# Power.net
KiCad netlist of a schematic drawn in Altium Designer
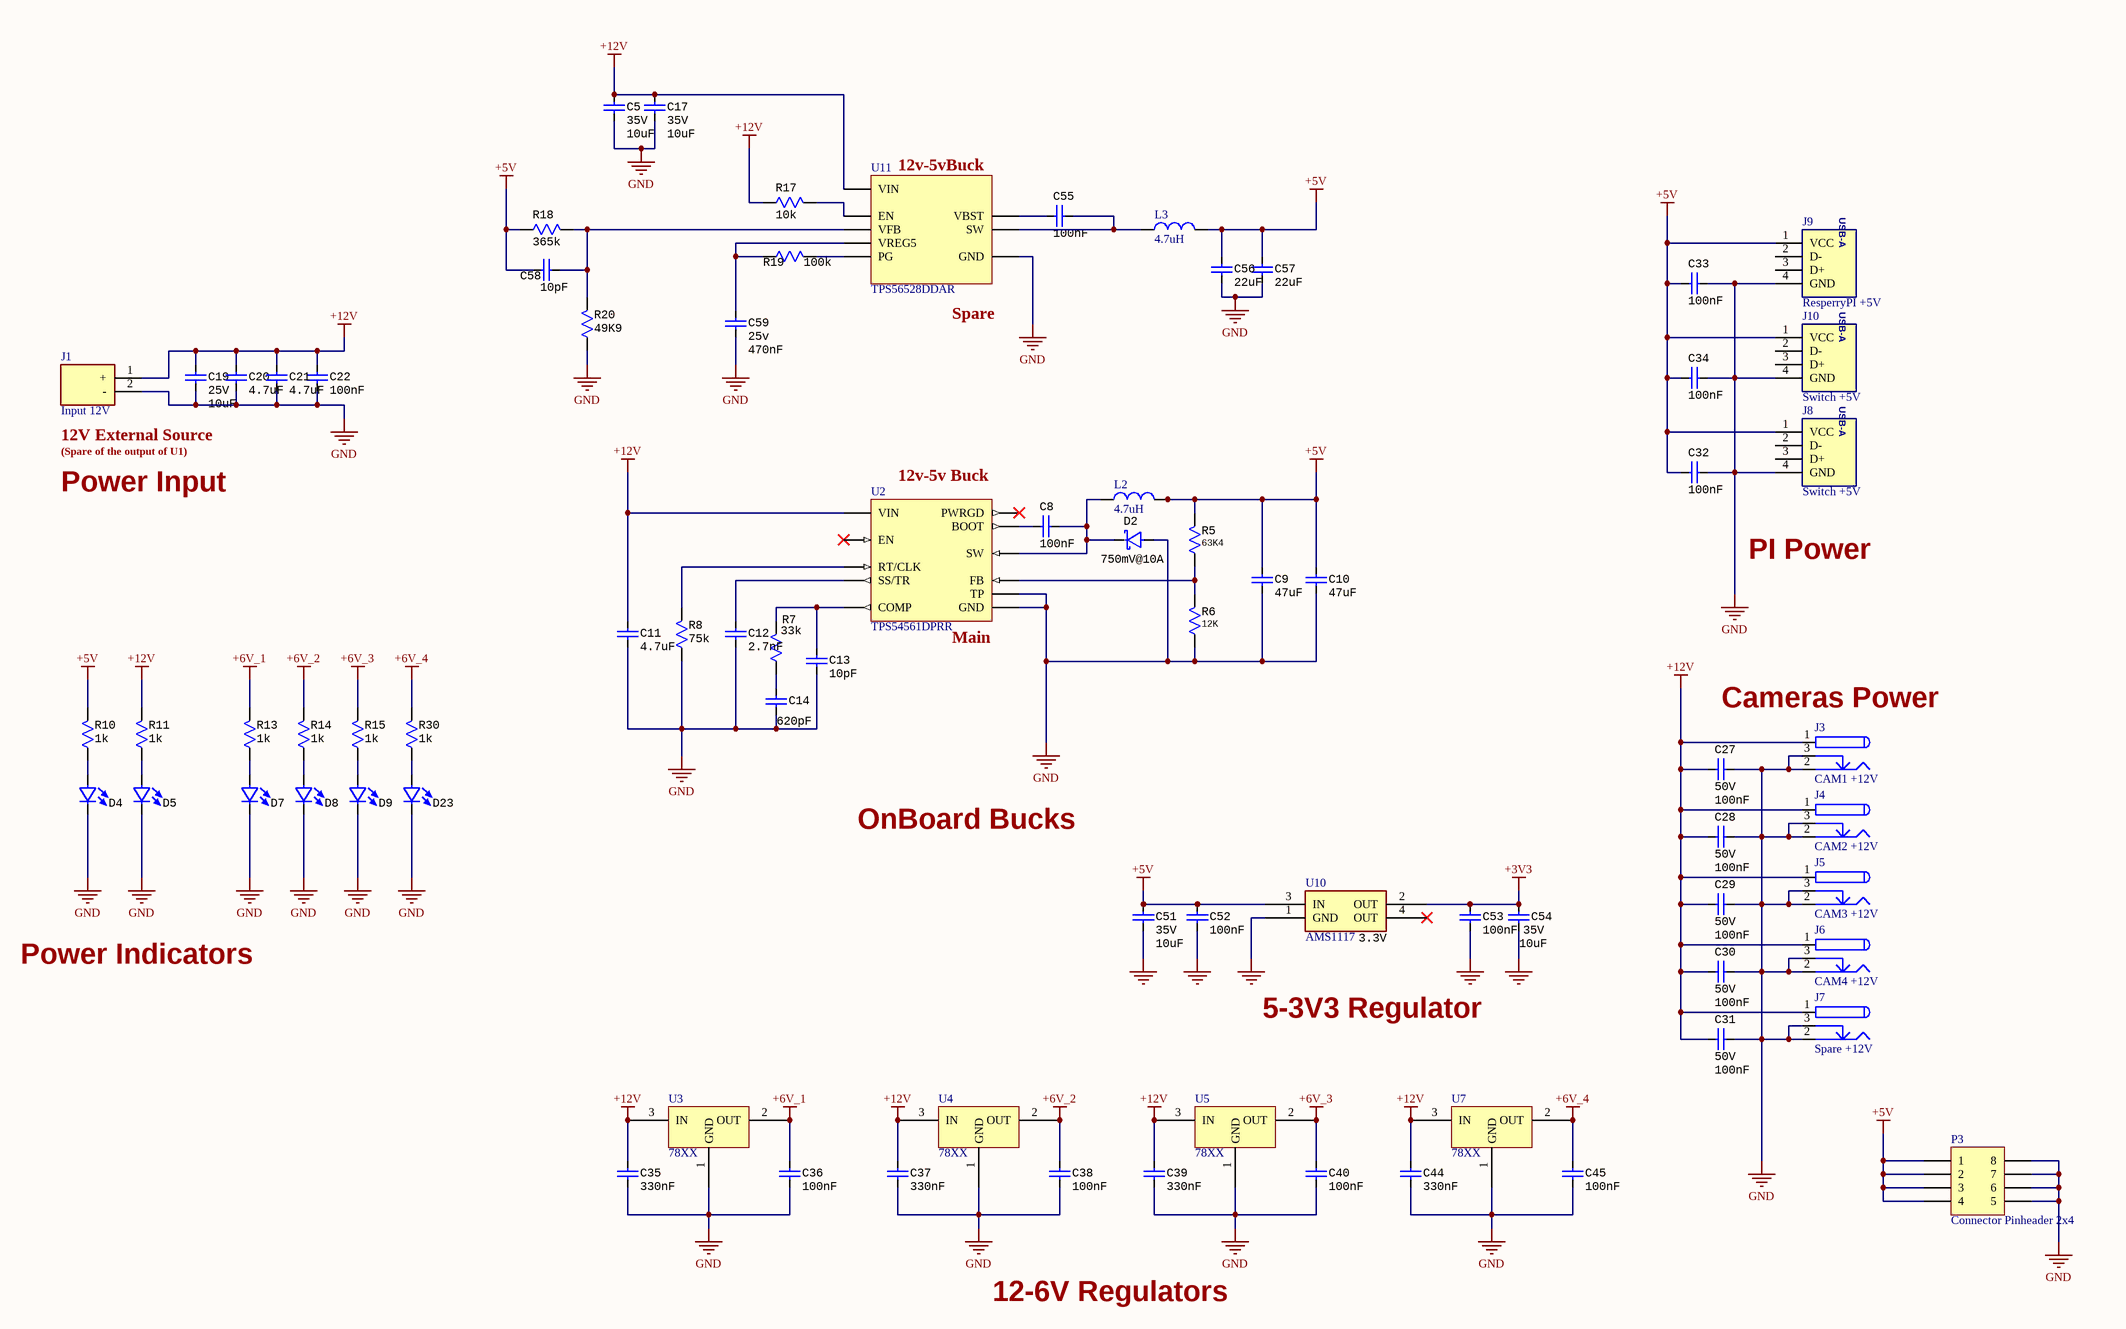
[diagram p0: Power.SchDoc]

(export (version "E")
  (design (tool "Eeschema 10.0.6"))
  (components
    (comp (ref "C5")
      (value "10uF")
      (footprint "CAP Ceramic SMD 0603")
      (description "Cap Ceramic 10uF 35V X5R 20% Pad SMD 0603 85C T/R")
      (fields
        (field (name "MANUFACTURER") "Murata")
        (field (name "MANUFACTURER PART NUMBER") "GRM188R6YA106MA73D")
        (field (name "VOLTAGE") "35V")
      )
      (libsource (lib "Passive") (part "CAP 0603 10uF 35V"))
    )
    (comp (ref "C8")
      (value "100nF")
      (footprint "CAP Ceramic SMD 0603")
      (description "0603 0.1 uF 100 V ±10% Tolerance X7R Multilayer Ceramic Capacitor")
      (fields
        (field (name "MANUFACTURER") "Yageo")
        (field (name "MANUFACTURER PART NUMBER") "CC0603KRX7R0BB104")
      )
      (libsource (lib "capacitor") (part "CAP 0603 100nF 100V"))
    )
    (comp (ref "C9")
      (value "47uF")
      (footprint "CAP Ceramic SMD 1206")
      (description "CAP CER 47UF 10V X5R 1206")
      (fields
        (field (name "MANUFACTURER") "Murata")
        (field (name "MANUFACTURER PART NUMBER") "GRM31CR61A476ME15L")
      )
      (libsource (lib "Passive") (part "CAP 1206 47uF 10V"))
    )
    (comp (ref "C10")
      (value "47uF")
      (footprint "CAP Ceramic SMD 1206")
      (description "CAP CER 47UF 10V X5R 1206")
      (fields
        (field (name "MANUFACTURER") "Murata")
        (field (name "MANUFACTURER PART NUMBER") "GRM31CR61A476ME15L")
      )
      (libsource (lib "Passive") (part "CAP 1206 47uF 10V"))
    )
    (comp (ref "C11")
      (value "4.7uF")
      (footprint "CAP Ceramic SMD 1206")
      (description "Cap Ceramic 4.7uF 100V X7S 10% SMD 1206 125°C Emboss T/R")
      (fields
        (field (name "MANUFACTURER PART NUMBER") "GRM31CC72A475KE11L")
        (field (name "MANUFACTURER") "Murata")
      )
      (libsource (lib "Passive") (part "CAP 1206 4.7uF 100V"))
    )
    (comp (ref "C12")
      (value "2.7nF")
      (footprint "CAP Ceramic SMD 0603")
      (description "0603 2.7 nF 50 V ±10 % Tolerance X7R SMT Multilayer Ceramic Capacitor")
      (fields
        (field (name "MANUFACTURER") "Yageo")
        (field (name "MANUFACTURER PART NUMBER") "CC0603KRX7R9BB272")
      )
      (libsource (lib "Passive") (part "CAP 0603 2.7nF 50V"))
    )
    (comp (ref "C13")
      (value "10pF")
      (footprint "CAP Ceramic SMD 0603")
      (description "Surface Mount Ceramic Multilayer Capacitor 10pF 5% C0G 50V 0603 Paper T/R")
      (fields
        (field (name "MANUFACTURER") "Yageo")
        (field (name "MANUFACTURER PART NUMBER") "CC0603JRNPO9BN100")
      )
      (libsource (lib "Passive") (part "CAP 0603 10pF 50V"))
    )
    (comp (ref "C14")
      (value "620pF")
      (footprint "CAP Ceramic SMD 0603")
      (description "Surface Mount Ceramic Multilayer Capacitor 620pF 5% C0G 50V 0603 Paper T/R")
      (fields
        (field (name "MANUFACTURER") "Yageo")
        (field (name "MANUFACTURER PART NUMBER") "CC0603JRNPO9BN621")
      )
      (libsource (lib "Passive") (part "CAP 0603 620pF 50V"))
    )
    (comp (ref "C17")
      (value "10uF")
      (footprint "CAP Ceramic SMD 0603")
      (description "Cap Ceramic 10uF 35V X5R 20% Pad SMD 0603 85C T/R")
      (fields
        (field (name "MANUFACTURER") "Murata")
        (field (name "MANUFACTURER PART NUMBER") "GRM188R6YA106MA73D")
        (field (name "VOLTAGE") "35V")
      )
      (libsource (lib "Passive") (part "CAP 0603 10uF 35V"))
    )
    (comp (ref "C19")
      (value "10uF")
      (footprint "CAP Ceramic SMD 1206")
      (description "Ceramic capacitor SMD-1206 10000nF (10uF) /25V X7R# K 10%, Samsung, RoHS/4k/")
      (fields
        (field (name "MANUFACTURER") "Samsung")
        (field (name "MANUFACTURER PART NUMBER") "CL31B106KAHNNNE")
        (field (name "VOLTAGE") "25V")
      )
      (libsource (lib "Passive") (part "CAP 1206 10uF 25V"))
    )
    (comp (ref "C20")
      (value "4.7uF")
      (footprint "CAP Ceramic SMD 1206")
      (description "Cap Ceramic 4.7uF 100V X7S 10% SMD 1206 125°C Emboss T/R")
      (fields
        (field (name "MANUFACTURER PART NUMBER") "GRM31CC72A475KE11L")
        (field (name "MANUFACTURER") "Murata")
      )
      (libsource (lib "Passive") (part "CAP 1206 4.7uF 100V"))
    )
    (comp (ref "C21")
      (value "4.7uF")
      (footprint "CAP Ceramic SMD 1206")
      (description "Cap Ceramic 4.7uF 100V X7S 10% SMD 1206 125°C Emboss T/R")
      (fields
        (field (name "MANUFACTURER PART NUMBER") "GRM31CC72A475KE11L")
        (field (name "MANUFACTURER") "Murata")
      )
      (libsource (lib "Passive") (part "CAP 1206 4.7uF 100V"))
    )
    (comp (ref "C22")
      (value "100nF")
      (footprint "CAP Ceramic SMD 0603")
      (description "0603 0.1 uF 100 V ±10% Tolerance X7R Multilayer Ceramic Capacitor")
      (fields
        (field (name "MANUFACTURER") "Yageo")
        (field (name "MANUFACTURER PART NUMBER") "CC0603KRX7R0BB104")
      )
      (libsource (lib "capacitor") (part "CAP 0603 100nF 100V"))
    )
    (comp (ref "C27")
      (value "100nF")
      (footprint "CAP Ceramic SMD 0603")
      (description "Multilayer Ceramic Capacitors MLCC Surface Mount 0603 0.1uF 50 Volts X7R 10%")
      (fields
        (field (name "MANUFACTURER") "Murata")
        (field (name "MANUFACTURER PART NUMBER") "GRM188R71H104KA93D")
        (field (name "VOLTAGE") "50V")
      )
      (libsource (lib "Passive") (part "CAP 0603 100nF 50V"))
    )
    (comp (ref "C28")
      (value "100nF")
      (footprint "CAP Ceramic SMD 0603")
      (description "Multilayer Ceramic Capacitors MLCC Surface Mount 0603 0.1uF 50 Volts X7R 10%")
      (fields
        (field (name "MANUFACTURER") "Murata")
        (field (name "MANUFACTURER PART NUMBER") "GRM188R71H104KA93D")
        (field (name "VOLTAGE") "50V")
      )
      (libsource (lib "Passive") (part "CAP 0603 100nF 50V"))
    )
    (comp (ref "C29")
      (value "100nF")
      (footprint "CAP Ceramic SMD 0603")
      (description "Multilayer Ceramic Capacitors MLCC Surface Mount 0603 0.1uF 50 Volts X7R 10%")
      (fields
        (field (name "MANUFACTURER") "Murata")
        (field (name "MANUFACTURER PART NUMBER") "GRM188R71H104KA93D")
        (field (name "VOLTAGE") "50V")
      )
      (libsource (lib "Passive") (part "CAP 0603 100nF 50V"))
    )
    (comp (ref "C30")
      (value "100nF")
      (footprint "CAP Ceramic SMD 0603")
      (description "Multilayer Ceramic Capacitors MLCC Surface Mount 0603 0.1uF 50 Volts X7R 10%")
      (fields
        (field (name "MANUFACTURER") "Murata")
        (field (name "MANUFACTURER PART NUMBER") "GRM188R71H104KA93D")
        (field (name "VOLTAGE") "50V")
      )
      (libsource (lib "Passive") (part "CAP 0603 100nF 50V"))
    )
    (comp (ref "C31")
      (value "100nF")
      (footprint "CAP Ceramic SMD 0603")
      (description "Multilayer Ceramic Capacitors MLCC Surface Mount 0603 0.1uF 50 Volts X7R 10%")
      (fields
        (field (name "MANUFACTURER") "Murata")
        (field (name "MANUFACTURER PART NUMBER") "GRM188R71H104KA93D")
        (field (name "VOLTAGE") "50V")
      )
      (libsource (lib "Passive") (part "CAP 0603 100nF 50V"))
    )
    (comp (ref "C32")
      (value "100nF")
      (footprint "CAP Ceramic SMD 0603")
      (description "0603 0.1 uF 100 V ±10% Tolerance X7R Multilayer Ceramic Capacitor")
      (fields
        (field (name "MANUFACTURER") "Yageo")
        (field (name "MANUFACTURER PART NUMBER") "CC0603KRX7R0BB104")
      )
      (libsource (lib "capacitor") (part "CAP 0603 100nF 100V"))
    )
    (comp (ref "C33")
      (value "100nF")
      (footprint "CAP Ceramic SMD 0603")
      (description "0603 0.1 uF 100 V ±10% Tolerance X7R Multilayer Ceramic Capacitor")
      (fields
        (field (name "MANUFACTURER") "Yageo")
        (field (name "MANUFACTURER PART NUMBER") "CC0603KRX7R0BB104")
      )
      (libsource (lib "capacitor") (part "CAP 0603 100nF 100V"))
    )
    (comp (ref "C34")
      (value "100nF")
      (footprint "CAP Ceramic SMD 0603")
      (description "0603 0.1 uF 100 V ±10% Tolerance X7R Multilayer Ceramic Capacitor")
      (fields
        (field (name "MANUFACTURER") "Yageo")
        (field (name "MANUFACTURER PART NUMBER") "CC0603KRX7R0BB104")
      )
      (libsource (lib "capacitor") (part "CAP 0603 100nF 100V"))
    )
    (comp (ref "C35")
      (value "330nF")
      (footprint "CAP Ceramic SMD 0603")
      (description "Multilayer Ceramic Capacitor, 0.33 uF, 50 V, ± 10%, X7R, 0603 [1608 Metric]")
      (fields
        (field (name "MANUFACTURER") "TDK")
        (field (name "MANUFACTURER PART NUMBER") "C1608X7R1H334K080AC")
      )
      (libsource (lib "Passive") (part "CAP 0603 330nF 50V"))
    )
    (comp (ref "C36")
      (value "100nF")
      (footprint "CAP Ceramic SMD 0603")
      (description "0603 0.1 uF 100 V ±10% Tolerance X7R Multilayer Ceramic Capacitor")
      (fields
        (field (name "MANUFACTURER") "Yageo")
        (field (name "MANUFACTURER PART NUMBER") "CC0603KRX7R0BB104")
      )
      (libsource (lib "Passive") (part "CAP 0603 100nF 100V"))
    )
    (comp (ref "C37")
      (value "330nF")
      (footprint "CAP Ceramic SMD 0603")
      (description "Multilayer Ceramic Capacitor, 0.33 uF, 50 V, ± 10%, X7R, 0603 [1608 Metric]")
      (fields
        (field (name "MANUFACTURER") "TDK")
        (field (name "MANUFACTURER PART NUMBER") "C1608X7R1H334K080AC")
      )
      (libsource (lib "Passive") (part "CAP 0603 330nF 50V"))
    )
    (comp (ref "C38")
      (value "100nF")
      (footprint "CAP Ceramic SMD 0603")
      (description "0603 0.1 uF 100 V ±10% Tolerance X7R Multilayer Ceramic Capacitor")
      (fields
        (field (name "MANUFACTURER") "Yageo")
        (field (name "MANUFACTURER PART NUMBER") "CC0603KRX7R0BB104")
      )
      (libsource (lib "Passive") (part "CAP 0603 100nF 100V"))
    )
    (comp (ref "C39")
      (value "330nF")
      (footprint "CAP Ceramic SMD 0603")
      (description "Multilayer Ceramic Capacitor, 0.33 uF, 50 V, ± 10%, X7R, 0603 [1608 Metric]")
      (fields
        (field (name "MANUFACTURER") "TDK")
        (field (name "MANUFACTURER PART NUMBER") "C1608X7R1H334K080AC")
      )
      (libsource (lib "Passive") (part "CAP 0603 330nF 50V"))
    )
    (comp (ref "C40")
      (value "100nF")
      (footprint "CAP Ceramic SMD 0603")
      (description "0603 0.1 uF 100 V ±10% Tolerance X7R Multilayer Ceramic Capacitor")
      (fields
        (field (name "MANUFACTURER") "Yageo")
        (field (name "MANUFACTURER PART NUMBER") "CC0603KRX7R0BB104")
      )
      (libsource (lib "Passive") (part "CAP 0603 100nF 100V"))
    )
    (comp (ref "C44")
      (value "330nF")
      (footprint "CAP Ceramic SMD 0603")
      (description "Multilayer Ceramic Capacitor, 0.33 uF, 50 V, ± 10%, X7R, 0603 [1608 Metric]")
      (fields
        (field (name "MANUFACTURER") "TDK")
        (field (name "MANUFACTURER PART NUMBER") "C1608X7R1H334K080AC")
      )
      (libsource (lib "Passive") (part "CAP 0603 330nF 50V"))
    )
    (comp (ref "C45")
      (value "100nF")
      (footprint "CAP Ceramic SMD 0603")
      (description "0603 0.1 uF 100 V ±10% Tolerance X7R Multilayer Ceramic Capacitor")
      (fields
        (field (name "MANUFACTURER") "Yageo")
        (field (name "MANUFACTURER PART NUMBER") "CC0603KRX7R0BB104")
      )
      (libsource (lib "Passive") (part "CAP 0603 100nF 100V"))
    )
    (comp (ref "C51")
      (value "10uF")
      (footprint "CAP Ceramic SMD 0603")
      (description "Cap Ceramic 10uF 35V X5R 20% Pad SMD 0603 85C T/R")
      (fields
        (field (name "MANUFACTURER") "Murata")
        (field (name "MANUFACTURER PART NUMBER") "GRM188R6YA106MA73D")
        (field (name "VOLTAGE") "35V")
      )
      (libsource (lib "Passive") (part "CAP 0603 10uF 35V"))
    )
    (comp (ref "C52")
      (value "100nF")
      (footprint "CAP Ceramic SMD 0603")
      (description "0603 0.1 uF 100 V ±10% Tolerance X7R Multilayer Ceramic Capacitor")
      (fields
        (field (name "MANUFACTURER") "Yageo")
        (field (name "MANUFACTURER PART NUMBER") "AC0603KRX7R0BB104")
      )
      (libsource (lib "capacitor") (part "CAP 0603 100nF 100V"))
    )
    (comp (ref "C53")
      (value "100nF")
      (footprint "CAP Ceramic SMD 0603")
      (description "0603 0.1 uF 100 V ±10% Tolerance X7R Multilayer Ceramic Capacitor")
      (fields
        (field (name "MANUFACTURER") "Yageo")
        (field (name "MANUFACTURER PART NUMBER") "AC0603KRX7R0BB104")
      )
      (libsource (lib "capacitor") (part "CAP 0603 100nF 100V"))
    )
    (comp (ref "C54")
      (value "10uF")
      (footprint "CAP Ceramic SMD 0603")
      (description "Cap Ceramic 10uF 35V X5R 20% Pad SMD 0603 85C T/R")
      (fields
        (field (name "MANUFACTURER") "Murata")
        (field (name "MANUFACTURER PART NUMBER") "GRM188R6YA106MA73D")
        (field (name "VOLTAGE") "35V")
      )
      (libsource (lib "Passive") (part "CAP 0603 10uF 35V"))
    )
    (comp (ref "C55")
      (value "100nF")
      (footprint "CAP Ceramic SMD 0603")
      (description "0603 0.1 uF 100 V ±10% Tolerance X7R Multilayer Ceramic Capacitor")
      (fields
        (field (name "MANUFACTURER") "Yageo")
        (field (name "MANUFACTURER PART NUMBER") "CC0603KRX7R0BB104")
      )
      (libsource (lib "Passive") (part "CAP 0603 100nF 100V"))
    )
    (comp (ref "C56")
      (value "22uF")
      (footprint "CAP Ceramic SMD 0603")
      (description "6.3V 22uF X5R ±20% 0603 Multilayer Ceramic Capacitors MLCC - SMD/SMT ROHS")
      (fields
        (field (name "MANUFACTURER") "YAGEO")
        (field (name "VOLTAGE") "6.3V")
        (field (name "CAPACITANCE") "22uF")
      )
      (libsource (lib "Passive") (part "CAP 0603 22uF 16V"))
    )
    (comp (ref "C57")
      (value "22uF")
      (footprint "CAP Ceramic SMD 0603")
      (description "6.3V 22uF X5R ±20% 0603 Multilayer Ceramic Capacitors MLCC - SMD/SMT ROHS")
      (fields
        (field (name "MANUFACTURER") "YAGEO")
        (field (name "VOLTAGE") "6.3V")
        (field (name "CAPACITANCE") "22uF")
      )
      (libsource (lib "Passive") (part "CAP 0603 22uF 16V"))
    )
    (comp (ref "C58")
      (value "10pF")
      (footprint "CAP Ceramic SMD 0603")
      (description "Surface Mount Ceramic Multilayer Capacitor 10pF 5% C0G 50V 0603 Paper T/R")
      (fields
        (field (name "MANUFACTURER") "Yageo")
        (field (name "MANUFACTURER PART NUMBER") "CC0603JRNPO9BN100")
      )
      (libsource (lib "Passive") (part "CAP 0603 10pF 50V"))
    )
    (comp (ref "C59")
      (value "470nF")
      (footprint "CAP Ceramic SMD 0603")
      (description "25V 470nF X7R 0603 Multilayer Ceramic Capacitors MLCC - SMD/SMT ROHS")
      (fields
        (field (name "MANUFACTURER") "Samwha Capacitor")
        (field (name "MANUFACTURER PART NUMBER") "CS1608X7R474K250NRB")
        (field (name "VOLTAGE") "25v")
      )
      (libsource (lib "capacitor") (part "CAP 0603 470F 25V"))
    )
    (comp (ref "D2")
      (value "750mV@10A")
      (footprint "TO-277")
      (description "100V 750mV@10A 10A TO-277 Schottky Barrier Diodes (SBD) ROHS")
      (fields (field (name "MANUFACTURER") "MDD") (field (name "MANUFACTURER PART NUMBER") "SB10100L"))
      (libsource (lib "diode") (part "Schottky 100V 750mV@10A"))
    )
    (comp (ref "D4")
      (value "~")
      (footprint "LED SMD 0805G")
      (description "emerald 0805 Light Emitting Diodes (LED) ROHS")
      (fields
        (field (name "MANUFACTURER") "FOSHAN Nationstar Optoelectronics")
        (field (name "MANUFACTURER PART NUMBER") "NCD0805G1")
      )
      (libsource (lib "diode") (part "LED 0805 Emerald"))
    )
    (comp (ref "D5")
      (value "~")
      (footprint "LED SMD 0805G")
      (description "emerald 0805 Light Emitting Diodes (LED) ROHS")
      (fields
        (field (name "MANUFACTURER") "FOSHAN Nationstar Optoelectronics")
        (field (name "MANUFACTURER PART NUMBER") "NCD0805G1")
      )
      (libsource (lib "diode") (part "LED 0805 Emerald"))
    )
    (comp (ref "D7")
      (value "~")
      (footprint "LED SMD 0805G")
      (description "emerald 0805 Light Emitting Diodes (LED) ROHS")
      (fields
        (field (name "MANUFACTURER") "FOSHAN Nationstar Optoelectronics")
        (field (name "MANUFACTURER PART NUMBER") "NCD0805G1")
      )
      (libsource (lib "diode") (part "LED 0805 Emerald"))
    )
    (comp (ref "D8")
      (value "~")
      (footprint "LED SMD 0805G")
      (description "emerald 0805 Light Emitting Diodes (LED) ROHS")
      (fields
        (field (name "MANUFACTURER") "FOSHAN Nationstar Optoelectronics")
        (field (name "MANUFACTURER PART NUMBER") "NCD0805G1")
      )
      (libsource (lib "diode") (part "LED 0805 Emerald"))
    )
    (comp (ref "D9")
      (value "~")
      (footprint "LED SMD 0805G")
      (description "emerald 0805 Light Emitting Diodes (LED) ROHS")
      (fields
        (field (name "MANUFACTURER") "FOSHAN Nationstar Optoelectronics")
        (field (name "MANUFACTURER PART NUMBER") "NCD0805G1")
      )
      (libsource (lib "diode") (part "LED 0805 Emerald"))
    )
    (comp (ref "D23")
      (value "~")
      (footprint "LED SMD 0805G")
      (description "emerald 0805 Light Emitting Diodes (LED) ROHS")
      (fields
        (field (name "MANUFACTURER") "FOSHAN Nationstar Optoelectronics")
        (field (name "MANUFACTURER PART NUMBER") "NCD0805G1")
      )
      (libsource (lib "diode") (part "LED 0805 Emerald"))
    )
    (comp (ref "J1")
      (value "Input 12V")
      (footprint "XT60PW-M")
      (description "Power Connectors ROHS")
      (fields
        (field (name "MANUFACTURER") "Changzhou Amass Elec")
        (field (name "MANUFACTURERPARTNUMBER") "XT60PW-M")
      )
      (libsource (lib "Power connectors") (part "XT60PW-M"))
    )
    (comp (ref "J3")
      (value "CAM1 +12V")
      (footprint "DC-005")
      (description "CIRCULAR DC POWER CONNECTOR\r\nRated Current: 7.5A\r\nRated Volatage: 20VDC")
      (libsource (lib "Power connectors") (part "DC_Socket"))
    )
    (comp (ref "J4")
      (value "CAM2 +12V")
      (footprint "DC-005")
      (description "CIRCULAR DC POWER CONNECTOR\r\nRated Current: 7.5A\r\nRated Volatage: 20VDC")
      (libsource (lib "Power connectors") (part "DC_Socket"))
    )
    (comp (ref "J5")
      (value "CAM3 +12V")
      (footprint "DC-005")
      (description "CIRCULAR DC POWER CONNECTOR\r\nRated Current: 7.5A\r\nRated Volatage: 20VDC")
      (libsource (lib "Power connectors") (part "DC_Socket"))
    )
    (comp (ref "J6")
      (value "CAM4 +12V")
      (footprint "DC-005")
      (description "CIRCULAR DC POWER CONNECTOR\r\nRated Current: 7.5A\r\nRated Volatage: 20VDC")
      (libsource (lib "Power connectors") (part "DC_Socket"))
    )
    (comp (ref "J7")
      (value "Spare +12V")
      (footprint "DC-005")
      (description "CIRCULAR DC POWER CONNECTOR\r\nRated Current: 7.5A\r\nRated Volatage: 20VDC")
      (libsource (lib "Power connectors") (part "DC_Socket"))
    )
    (comp (ref "J8")
      (value "Switch +5V")
      (footprint "USB-A/S_A")
      (libsource (lib "USB connectors") (part "Connector_USB-A"))
    )
    (comp (ref "J9")
      (value "ResperryPI +5V")
      (footprint "USB-A/S_A")
      (libsource (lib "USB connectors") (part "Connector_USB-A"))
    )
    (comp (ref "J10")
      (value "Switch +5V")
      (footprint "USB-A/S_A")
      (libsource (lib "USB connectors") (part "Connector_USB-A"))
    )
    (comp (ref "L2")
      (value "4.7uH")
      (footprint "XLS1040")
      (description "9A 4.7uH ±20% 17mΩ 15A SMD,11.5x10x3.8mm Power Inductors ROHS")
      (fields
        (field (name "MANUFACTURER") "Cjiang")
        (field (name "MANUFACTURER PART NUMBER") "FXL1040-4R7-M")
      )
      (libsource (lib "Passive") (part "IND 0403 4.7uH 20%"))
    )
    (comp (ref "L3")
      (value "4.7uH")
      (footprint "XLS1040")
      (description "9A 4.7uH ±20% 17mΩ 15A SMD,11.5x10x3.8mm Power Inductors ROHS")
      (fields
        (field (name "MANUFACTURER") "Cjiang")
        (field (name "MANUFACTURER PART NUMBER") "FXL1040-4R7-M")
      )
      (libsource (lib "Passive") (part "IND 0403 4.7uH 20%"))
    )
    (comp (ref "P3")
      (value "Connector Pinheader 2x4")
      (footprint "Header 2.54_2X4")
      (description "Header_2X4")
      (libsource (lib "Signal connectors") (part "Connector Pinheader 2x4"))
    )
    (comp (ref "R5")
      (value "63K4")
      (footprint "RES SMD 0603")
      (fields
        (field (name "MANUFACTURER") "Yageo")
        (field (name "MANUFACTURER PART NUMBER") "AC0603FR-0763K4L")
        (field (name "TOLERANCE") "1%")
      )
      (libsource (lib "Passive") (part "RES 0603 63K4 1%"))
    )
    (comp (ref "R6")
      (value "12K")
      (footprint "RES SMD 0603")
      (fields
        (field (name "MANUFACTURER") "Yageo")
        (field (name "MANUFACTURER PART NUMBER") "RC0603FR-0712KL")
        (field (name "TOLERANCE") "1%")
      )
      (libsource (lib "Passive") (part "RES 0603 12K 1%"))
    )
    (comp (ref "R7")
      (value "33k")
      (footprint "RES SMD 0603")
      (fields
        (field (name "MANUFACTURER") "Uniroyal")
        (field (name "MANUFACTURER PART NUMBER") "0603WAF3902T5E")
      )
      (libsource (lib "Passive") (part "RES 0603 39k 1%"))
    )
    (comp (ref "R8")
      (value "75k")
      (footprint "RES SMD 0603")
      (description "Res Thick Film 0603 75K Ohm 1% 0.1W(1/10W) ±100ppm/C Pad SMD Automotive T/R")
      (fields
        (field (name "MANUFACTURER") "Panasonic")
        (field (name "MANUFACTURER PART NUMBER") "ERJ3RBD7502V")
      )
      (libsource (lib "Passive") (part "RES 0603 75k 1%"))
    )
    (comp (ref "R10")
      (value "1k")
      (footprint "RES SMD 0603")
      (description "Res Thick Film 0603 1K Ohm 1% 1/10W ±100ppm/°C Molded SMD Punched Carrier T/R")
      (fields
        (field (name "MANUFACTURER") "Panasonic")
        (field (name "MANUFACTURER PART NUMBER") "ERJ3EKF1001V")
      )
      (libsource (lib "Passive") (part "RES 0603 1k 1%"))
    )
    (comp (ref "R11")
      (value "1k")
      (footprint "RES SMD 0603")
      (description "Res Thick Film 0603 1K Ohm 1% 1/10W ±100ppm/°C Molded SMD Punched Carrier T/R")
      (fields
        (field (name "MANUFACTURER") "Panasonic")
        (field (name "MANUFACTURER PART NUMBER") "ERJ3EKF1001V")
      )
      (libsource (lib "Passive") (part "RES 0603 1k 1%"))
    )
    (comp (ref "R13")
      (value "1k")
      (footprint "RES SMD 0603")
      (description "Res Thick Film 0603 1K Ohm 1% 1/10W ±100ppm/°C Molded SMD Punched Carrier T/R")
      (fields
        (field (name "MANUFACTURER") "Panasonic")
        (field (name "MANUFACTURER PART NUMBER") "ERJ3EKF1001V")
      )
      (libsource (lib "Passive") (part "RES 0603 1k 1%"))
    )
    (comp (ref "R14")
      (value "1k")
      (footprint "RES SMD 0603")
      (description "Res Thick Film 0603 1K Ohm 1% 1/10W ±100ppm/°C Molded SMD Punched Carrier T/R")
      (fields
        (field (name "MANUFACTURER") "Panasonic")
        (field (name "MANUFACTURER PART NUMBER") "ERJ3EKF1001V")
      )
      (libsource (lib "Passive") (part "RES 0603 1k 1%"))
    )
    (comp (ref "R15")
      (value "1k")
      (footprint "RES SMD 0603")
      (description "Res Thick Film 0603 1K Ohm 1% 1/10W ±100ppm/°C Molded SMD Punched Carrier T/R")
      (fields
        (field (name "MANUFACTURER") "Panasonic")
        (field (name "MANUFACTURER PART NUMBER") "ERJ3EKF1001V")
      )
      (libsource (lib "Passive") (part "RES 0603 1k 1%"))
    )
    (comp (ref "R17")
      (value "10k")
      (footprint "RES SMD 0603")
      (description "Res Thick Film 0603 10K Ohm 1% 1/10W ±100ppm/°C Molded SMD Punched Carrier T/R")
      (fields
        (field (name "MANUFACTURER") "Panasonic")
        (field (name "MANUFACTURER PART NUMBER") "ERJ3EKF1002V")
      )
      (libsource (lib "Passive") (part "RES 0603 10k 1%"))
    )
    (comp (ref "R18")
      (value "365k")
      (footprint "RES SMD 0603")
      (description "100mW Thin Film Resistor ±25ppm/℃ ±0.1% 365kΩ 0603 Chip Resistor - Surface Mount ROHS")
      (fields
        (field (name "MANUFACTURER") "YAGEO")
        (field (name "MANUFACTURER PART NUMBER") "RT0603BRD07365KL")
      )
      (libsource (lib "resistor") (part "RES 0603 365k 0.1%"))
    )
    (comp (ref "R19")
      (value "100k")
      (footprint "RES SMD 0603")
      (description "RES SMD 100K OHM 1% 1/10W 0603")
      (fields
        (field (name "MANUFACTURER") "Panasonic")
        (field (name "MANUFACTURER PART NUMBER") "ERJ3EKF1003V")
        (field (name "RESISTANCE") "100k")
      )
      (libsource (lib "Passive") (part "RES 0603 100k 1%"))
    )
    (comp (ref "R20")
      (value "49K9")
      (footprint "RES SMD 0603")
      (fields
        (field (name "MANUFACTURER") "Yageo Phycomp")
        (field (name "MANUFACTURER PART NUMBER") "RC0603FR-0749K9L")
        (field (name "TOLERANCE") "1%")
      )
      (libsource (lib "Passive") (part "RES 0603 49K9 1%"))
    )
    (comp (ref "R30")
      (value "1k")
      (footprint "RES SMD 0603")
      (description "Res Thick Film 0603 1K Ohm 1% 1/10W ±100ppm/°C Molded SMD Punched Carrier T/R")
      (fields
        (field (name "MANUFACTURER") "Panasonic")
        (field (name "MANUFACTURER PART NUMBER") "ERJ3EKF1001V")
      )
      (libsource (lib "Passive") (part "RES 0603 1k 1%"))
    )
    (comp (ref "U2")
      (value "TPS54561DPRR")
      (footprint "TPS54561DPRR")
      (description "4.5V to 60V Input 5A Step-Down DC-DC Converter With Soft-Start and Eco-mode 10-WSON -40 to 125")
      (fields (field (name "MANUFACTURER") "Texas Instruments"))
      (libsource (lib "PMIC") (part "TPS54561DPRR"))
    )
    (comp (ref "U3")
      (value "78XX")
      (footprint "Linear reagulator SMD TO252")
      (libsource (lib "PMIC") (part "78XX"))
    )
    (comp (ref "U4")
      (value "78XX")
      (footprint "Linear reagulator SMD TO252")
      (libsource (lib "PMIC") (part "78XX"))
    )
    (comp (ref "U5")
      (value "78XX")
      (footprint "Linear reagulator SMD TO252")
      (libsource (lib "PMIC") (part "78XX"))
    )
    (comp (ref "U7")
      (value "78XX")
      (footprint "Linear reagulator SMD TO252")
      (libsource (lib "PMIC") (part "78XX"))
    )
    (comp (ref "U10")
      (value "AMS1117")
      (footprint "Linear reagulator SMD AMS1117 - duplicate")
      (fields
        (field (name "MANUFACTURER") "Advanced Monolithic Systems")
        (field (name "VOLTAGE OUTPUT") "3.3V")
      )
      (libsource (lib "Linear regulator") (part "AMS1117"))
    )
    (comp (ref "U11")
      (value "TPS56528DDAR")
      (footprint "TPS56528DDAR")
      (description "Step-down type Adjustable 600mV~7V 5A 4.5V~18V SOIC-8-EP DC-DC Converters ROHS")
      (fields (field (name "MANUFACTURER") "Texas Instruments"))
      (libsource (lib "PMIC") (part "TPS56528DDAR"))
    )
  )
  (nets
    (net (code "1") (name "+3V3") (class "Default")
      (node (ref "C53") (pin "1") (pinfunction "1_1") (pintype "passive"))
      (node (ref "C54") (pin "1") (pinfunction "1_1") (pintype "passive"))
      (node (ref "U10") (pin "2") (pinfunction "OUT_2") (pintype "passive"))
    )
    (net (code "2") (name "+5V") (class "Default")
      (node (ref "C10") (pin "1") (pinfunction "1_1") (pintype "passive"))
      (node (ref "C32") (pin "2") (pinfunction "2_2") (pintype "passive"))
      (node (ref "C33") (pin "2") (pinfunction "2_2") (pintype "passive"))
      (node (ref "C34") (pin "2") (pinfunction "2_2") (pintype "passive"))
      (node (ref "C51") (pin "1") (pinfunction "1_1") (pintype "passive"))
      (node (ref "C52") (pin "1") (pinfunction "1_1") (pintype "passive"))
      (node (ref "C56") (pin "1") (pinfunction "1_1") (pintype "passive"))
      (node (ref "C57") (pin "1") (pinfunction "1_1") (pintype "passive"))
      (node (ref "C58") (pin "1") (pinfunction "1_1") (pintype "passive"))
      (node (ref "C9") (pin "1") (pinfunction "1_1") (pintype "passive"))
      (node (ref "J10") (pin "1") (pinfunction "VCC_1") (pintype "passive"))
      (node (ref "J8") (pin "1") (pinfunction "VCC_1") (pintype "passive"))
      (node (ref "J9") (pin "1") (pinfunction "VCC_1") (pintype "passive"))
      (node (ref "L2") (pin "1") (pinfunction "1_1") (pintype "passive"))
      (node (ref "L3") (pin "1") (pinfunction "1_1") (pintype "passive"))
      (node (ref "P3") (pin "1") (pinfunction "1_1") (pintype "passive"))
      (node (ref "P3") (pin "2") (pinfunction "2_2") (pintype "passive"))
      (node (ref "P3") (pin "3") (pinfunction "3_3") (pintype "passive"))
      (node (ref "P3") (pin "4") (pinfunction "4_4") (pintype "passive"))
      (node (ref "R10") (pin "2") (pinfunction "2_2") (pintype "passive"))
      (node (ref "R18") (pin "1") (pinfunction "1_1") (pintype "passive"))
      (node (ref "R5") (pin "2") (pinfunction "2_2") (pintype "passive"))
      (node (ref "U10") (pin "3") (pinfunction "IN_3") (pintype "passive"))
    )
    (net (code "3") (name "+6V_1") (class "Default")
      (node (ref "C36") (pin "1") (pinfunction "1_1") (pintype "passive"))
      (node (ref "R13") (pin "2") (pinfunction "2_2") (pintype "passive"))
      (node (ref "U3") (pin "2") (pinfunction "OUT_2") (pintype "passive"))
    )
    (net (code "4") (name "+6V_2") (class "Default")
      (node (ref "C38") (pin "1") (pinfunction "1_1") (pintype "passive"))
      (node (ref "R14") (pin "2") (pinfunction "2_2") (pintype "passive"))
      (node (ref "U4") (pin "2") (pinfunction "OUT_2") (pintype "passive"))
    )
    (net (code "5") (name "+6V_3") (class "Default")
      (node (ref "C40") (pin "1") (pinfunction "1_1") (pintype "passive"))
      (node (ref "R15") (pin "2") (pinfunction "2_2") (pintype "passive"))
      (node (ref "U5") (pin "2") (pinfunction "OUT_2") (pintype "passive"))
    )
    (net (code "6") (name "+6V_4") (class "Default")
      (node (ref "C45") (pin "1") (pinfunction "1_1") (pintype "passive"))
      (node (ref "R30") (pin "2") (pinfunction "2_2") (pintype "passive"))
      (node (ref "U7") (pin "2") (pinfunction "OUT_2") (pintype "passive"))
    )
    (net (code "7") (name "+12V") (class "Default")
      (node (ref "C11") (pin "1") (pinfunction "1_1") (pintype "passive"))
      (node (ref "C17") (pin "1") (pinfunction "1_1") (pintype "passive"))
      (node (ref "C19") (pin "1") (pinfunction "1_1") (pintype "passive"))
      (node (ref "C20") (pin "1") (pinfunction "1_1") (pintype "passive"))
      (node (ref "C21") (pin "1") (pinfunction "1_1") (pintype "passive"))
      (node (ref "C22") (pin "1") (pinfunction "1_1") (pintype "passive"))
      (node (ref "C27") (pin "1") (pinfunction "1_1") (pintype "passive"))
      (node (ref "C28") (pin "1") (pinfunction "1_1") (pintype "passive"))
      (node (ref "C29") (pin "1") (pinfunction "1_1") (pintype "passive"))
      (node (ref "C30") (pin "1") (pinfunction "1_1") (pintype "passive"))
      (node (ref "C31") (pin "1") (pinfunction "1_1") (pintype "passive"))
      (node (ref "C35") (pin "1") (pinfunction "1_1") (pintype "passive"))
      (node (ref "C37") (pin "1") (pinfunction "1_1") (pintype "passive"))
      (node (ref "C39") (pin "1") (pinfunction "1_1") (pintype "passive"))
      (node (ref "C44") (pin "1") (pinfunction "1_1") (pintype "passive"))
      (node (ref "C5") (pin "1") (pinfunction "1_1") (pintype "passive"))
      (node (ref "J1") (pin "1") (pinfunction "+_1") (pintype "passive"))
      (node (ref "J3") (pin "1") (pinfunction "1_1") (pintype "power_in"))
      (node (ref "J4") (pin "1") (pinfunction "1_1") (pintype "power_in"))
      (node (ref "J5") (pin "1") (pinfunction "1_1") (pintype "power_in"))
      (node (ref "J6") (pin "1") (pinfunction "1_1") (pintype "power_in"))
      (node (ref "J7") (pin "1") (pinfunction "1_1") (pintype "power_in"))
      (node (ref "R11") (pin "2") (pinfunction "2_2") (pintype "passive"))
      (node (ref "R17") (pin "1") (pinfunction "1_1") (pintype "passive"))
      (node (ref "U11") (pin "8") (pinfunction "VIN_8") (pintype "passive"))
      (node (ref "U2") (pin "2") (pinfunction "VIN_2") (pintype "power_in"))
      (node (ref "U3") (pin "3") (pinfunction "IN_3") (pintype "passive"))
      (node (ref "U4") (pin "3") (pinfunction "IN_3") (pintype "passive"))
      (node (ref "U5") (pin "3") (pinfunction "IN_3") (pintype "passive"))
      (node (ref "U7") (pin "3") (pinfunction "IN_3") (pintype "passive"))
    )
    (net (code "8") (name "GND") (class "Default")
      (node (ref "C10") (pin "2") (pinfunction "2_2") (pintype "passive"))
      (node (ref "C11") (pin "2") (pinfunction "2_2") (pintype "passive"))
      (node (ref "C12") (pin "2") (pinfunction "2_2") (pintype "passive"))
      (node (ref "C13") (pin "2") (pinfunction "2_2") (pintype "passive"))
      (node (ref "C14") (pin "2") (pinfunction "2_2") (pintype "passive"))
      (node (ref "C17") (pin "2") (pinfunction "2_2") (pintype "passive"))
      (node (ref "C19") (pin "2") (pinfunction "2_2") (pintype "passive"))
      (node (ref "C20") (pin "2") (pinfunction "2_2") (pintype "passive"))
      (node (ref "C21") (pin "2") (pinfunction "2_2") (pintype "passive"))
      (node (ref "C22") (pin "2") (pinfunction "2_2") (pintype "passive"))
      (node (ref "C27") (pin "2") (pinfunction "2_2") (pintype "passive"))
      (node (ref "C28") (pin "2") (pinfunction "2_2") (pintype "passive"))
      (node (ref "C29") (pin "2") (pinfunction "2_2") (pintype "passive"))
      (node (ref "C30") (pin "2") (pinfunction "2_2") (pintype "passive"))
      (node (ref "C31") (pin "2") (pinfunction "2_2") (pintype "passive"))
      (node (ref "C32") (pin "1") (pinfunction "1_1") (pintype "passive"))
      (node (ref "C33") (pin "1") (pinfunction "1_1") (pintype "passive"))
      (node (ref "C34") (pin "1") (pinfunction "1_1") (pintype "passive"))
      (node (ref "C35") (pin "2") (pinfunction "2_2") (pintype "passive"))
      (node (ref "C36") (pin "2") (pinfunction "2_2") (pintype "passive"))
      (node (ref "C37") (pin "2") (pinfunction "2_2") (pintype "passive"))
      (node (ref "C38") (pin "2") (pinfunction "2_2") (pintype "passive"))
      (node (ref "C39") (pin "2") (pinfunction "2_2") (pintype "passive"))
      (node (ref "C40") (pin "2") (pinfunction "2_2") (pintype "passive"))
      (node (ref "C44") (pin "2") (pinfunction "2_2") (pintype "passive"))
      (node (ref "C45") (pin "2") (pinfunction "2_2") (pintype "passive"))
      (node (ref "C5") (pin "2") (pinfunction "2_2") (pintype "passive"))
      (node (ref "C51") (pin "2") (pinfunction "2_2") (pintype "passive"))
      (node (ref "C52") (pin "2") (pinfunction "2_2") (pintype "passive"))
      (node (ref "C53") (pin "2") (pinfunction "2_2") (pintype "passive"))
      (node (ref "C54") (pin "2") (pinfunction "2_2") (pintype "passive"))
      (node (ref "C56") (pin "2") (pinfunction "2_2") (pintype "passive"))
      (node (ref "C57") (pin "2") (pinfunction "2_2") (pintype "passive"))
      (node (ref "C59") (pin "2") (pinfunction "2_2") (pintype "passive"))
      (node (ref "C9") (pin "2") (pinfunction "2_2") (pintype "passive"))
      (node (ref "D2") (pin "1") (pinfunction "1_1") (pintype "passive"))
      (node (ref "D23") (pin "2") (pinfunction "2_2") (pintype "passive"))
      (node (ref "D4") (pin "2") (pinfunction "2_2") (pintype "passive"))
      (node (ref "D5") (pin "2") (pinfunction "2_2") (pintype "passive"))
      (node (ref "D7") (pin "2") (pinfunction "2_2") (pintype "passive"))
      (node (ref "D8") (pin "2") (pinfunction "2_2") (pintype "passive"))
      (node (ref "D9") (pin "2") (pinfunction "2_2") (pintype "passive"))
      (node (ref "J1") (pin "2") (pinfunction "-_2") (pintype "passive"))
      (node (ref "J10") (pin "4") (pinfunction "GND_4") (pintype "passive"))
      (node (ref "J3") (pin "2") (pinfunction "2_2") (pintype "power_in"))
      (node (ref "J3") (pin "3") (pinfunction "3_3") (pintype "power_in"))
      (node (ref "J4") (pin "2") (pinfunction "2_2") (pintype "power_in"))
      (node (ref "J4") (pin "3") (pinfunction "3_3") (pintype "power_in"))
      (node (ref "J5") (pin "2") (pinfunction "2_2") (pintype "power_in"))
      (node (ref "J5") (pin "3") (pinfunction "3_3") (pintype "power_in"))
      (node (ref "J6") (pin "2") (pinfunction "2_2") (pintype "power_in"))
      (node (ref "J6") (pin "3") (pinfunction "3_3") (pintype "power_in"))
      (node (ref "J7") (pin "2") (pinfunction "2_2") (pintype "power_in"))
      (node (ref "J7") (pin "3") (pinfunction "3_3") (pintype "power_in"))
      (node (ref "J8") (pin "4") (pinfunction "GND_4") (pintype "passive"))
      (node (ref "J9") (pin "4") (pinfunction "GND_4") (pintype "passive"))
      (node (ref "P3") (pin "5") (pinfunction "5_5") (pintype "passive"))
      (node (ref "P3") (pin "6") (pinfunction "6_6") (pintype "passive"))
      (node (ref "P3") (pin "7") (pinfunction "7_7") (pintype "passive"))
      (node (ref "P3") (pin "8") (pinfunction "8_8") (pintype "passive"))
      (node (ref "R20") (pin "1") (pinfunction "1_1") (pintype "passive"))
      (node (ref "R6") (pin "1") (pinfunction "1_1") (pintype "passive"))
      (node (ref "R8") (pin "1") (pinfunction "1_1") (pintype "passive"))
      (node (ref "U10") (pin "1") (pinfunction "GND_1") (pintype "passive"))
      (node (ref "U11") (pin "5") (pinfunction "GND_5") (pintype "passive"))
      (node (ref "U2") (pin "11") (pinfunction "TP_11") (pintype "power_in"))
      (node (ref "U2") (pin "8") (pinfunction "GND_8") (pintype "power_in"))
      (node (ref "U3") (pin "1") (pinfunction "GND_1") (pintype "passive"))
      (node (ref "U4") (pin "1") (pinfunction "GND_1") (pintype "passive"))
      (node (ref "U5") (pin "1") (pinfunction "GND_1") (pintype "passive"))
      (node (ref "U7") (pin "1") (pinfunction "GND_1") (pintype "passive"))
    )
    (net (code "9") (name "Net-(C14-Pad1)") (class "Default")
      (node (ref "C14") (pin "1") (pinfunction "1_1") (pintype "passive"))
      (node (ref "R7") (pin "1") (pinfunction "1_1") (pintype "passive"))
    )
    (net (code "10") (name "Net-(D4-Pad1)") (class "Default")
      (node (ref "D4") (pin "1") (pinfunction "1_1") (pintype "passive"))
      (node (ref "R10") (pin "1") (pinfunction "1_1") (pintype "passive"))
    )
    (net (code "11") (name "Net-(D5-Pad1)") (class "Default")
      (node (ref "D5") (pin "1") (pinfunction "1_1") (pintype "passive"))
      (node (ref "R11") (pin "1") (pinfunction "1_1") (pintype "passive"))
    )
    (net (code "12") (name "Net-(D7-Pad1)") (class "Default")
      (node (ref "D7") (pin "1") (pinfunction "1_1") (pintype "passive"))
      (node (ref "R13") (pin "1") (pinfunction "1_1") (pintype "passive"))
    )
    (net (code "13") (name "Net-(D8-Pad1)") (class "Default")
      (node (ref "D8") (pin "1") (pinfunction "1_1") (pintype "passive"))
      (node (ref "R14") (pin "1") (pinfunction "1_1") (pintype "passive"))
    )
    (net (code "14") (name "Net-(D9-Pad1)") (class "Default")
      (node (ref "D9") (pin "1") (pinfunction "1_1") (pintype "passive"))
      (node (ref "R15") (pin "1") (pinfunction "1_1") (pintype "passive"))
    )
    (net (code "15") (name "Net-(D23-Pad1)") (class "Default")
      (node (ref "D23") (pin "1") (pinfunction "1_1") (pintype "passive"))
      (node (ref "R30") (pin "1") (pinfunction "1_1") (pintype "passive"))
    )
    (net (code "16") (name "Net-(U2-BOOT)") (class "Default")
      (node (ref "C8") (pin "1") (pinfunction "1_1") (pintype "passive"))
      (node (ref "U2") (pin "1") (pinfunction "BOOT_1") (pintype "output"))
    )
    (net (code "17") (name "Net-(U2-COMP)") (class "Default")
      (node (ref "C13") (pin "1") (pinfunction "1_1") (pintype "passive"))
      (node (ref "R7") (pin "2") (pinfunction "2_2") (pintype "passive"))
      (node (ref "U2") (pin "7") (pinfunction "COMP_7") (pintype "output"))
    )
    (net (code "18") (name "Net-(U2-FB)") (class "Default")
      (node (ref "R5") (pin "1") (pinfunction "1_1") (pintype "passive"))
      (node (ref "R6") (pin "2") (pinfunction "2_2") (pintype "passive"))
      (node (ref "U2") (pin "6") (pinfunction "FB_6") (pintype "input"))
    )
    (net (code "19") (name "Net-(U2-RT{slash}CLK)") (class "Default")
      (node (ref "R8") (pin "2") (pinfunction "2_2") (pintype "passive"))
      (node (ref "U2") (pin "5") (pinfunction "RT/CLK_5") (pintype "input"))
    )
    (net (code "20") (name "Net-(U2-SS{slash}TR)") (class "Default")
      (node (ref "C12") (pin "1") (pinfunction "1_1") (pintype "passive"))
      (node (ref "U2") (pin "4") (pinfunction "SS/TR_4") (pintype "output"))
    )
    (net (code "21") (name "Net-(U2-SW)") (class "Default")
      (node (ref "C8") (pin "2") (pinfunction "2_2") (pintype "passive"))
      (node (ref "D2") (pin "2") (pinfunction "2_2") (pintype "passive"))
      (node (ref "L2") (pin "2") (pinfunction "2_2") (pintype "passive"))
      (node (ref "U2") (pin "9") (pinfunction "SW_9") (pintype "input"))
    )
    (net (code "22") (name "Net-(U11-EN)") (class "Default")
      (node (ref "R17") (pin "2") (pinfunction "2_2") (pintype "passive"))
      (node (ref "U11") (pin "1") (pinfunction "EN_1") (pintype "passive"))
    )
    (net (code "23") (name "Net-(U11-PG)") (class "Default")
      (node (ref "R19") (pin "2") (pinfunction "2_2") (pintype "passive"))
      (node (ref "U11") (pin "4") (pinfunction "PG_4") (pintype "passive"))
    )
    (net (code "24") (name "Net-(U11-SW)") (class "Default")
      (node (ref "C55") (pin "2") (pinfunction "2_2") (pintype "passive"))
      (node (ref "L3") (pin "2") (pinfunction "2_2") (pintype "passive"))
      (node (ref "U11") (pin "6") (pinfunction "SW_6") (pintype "passive"))
    )
    (net (code "25") (name "Net-(U11-VBST)") (class "Default")
      (node (ref "C55") (pin "1") (pinfunction "1_1") (pintype "passive"))
      (node (ref "U11") (pin "7") (pinfunction "VBST_7") (pintype "passive"))
    )
    (net (code "26") (name "Net-(U11-VFB)") (class "Default")
      (node (ref "C58") (pin "2") (pinfunction "2_2") (pintype "passive"))
      (node (ref "R18") (pin "2") (pinfunction "2_2") (pintype "passive"))
      (node (ref "R20") (pin "2") (pinfunction "2_2") (pintype "passive"))
      (node (ref "U11") (pin "2") (pinfunction "VFB_2") (pintype "passive"))
    )
    (net (code "27") (name "Net-(U11-VREG5)") (class "Default")
      (node (ref "C59") (pin "1") (pinfunction "1_1") (pintype "passive"))
      (node (ref "R19") (pin "1") (pinfunction "1_1") (pintype "passive"))
      (node (ref "U11") (pin "3") (pinfunction "VREG5_3") (pintype "passive"))
    )
    (net (code "28") (name "unconnected-(J8-D+-Pad3)") (class "Default")
      (node (ref "J8") (pin "3") (pinfunction "D+_3") (pintype "passive"))
    )
    (net (code "29") (name "unconnected-(J8-D--Pad2)") (class "Default")
      (node (ref "J8") (pin "2") (pinfunction "D-_2") (pintype "passive"))
    )
    (net (code "30") (name "unconnected-(J9-D+-Pad3)") (class "Default")
      (node (ref "J9") (pin "3") (pinfunction "D+_3") (pintype "passive"))
    )
    (net (code "31") (name "unconnected-(J9-D--Pad2)") (class "Default")
      (node (ref "J9") (pin "2") (pinfunction "D-_2") (pintype "passive"))
    )
    (net (code "32") (name "unconnected-(J10-D+-Pad3)") (class "Default")
      (node (ref "J10") (pin "3") (pinfunction "D+_3") (pintype "passive"))
    )
    (net (code "33") (name "unconnected-(J10-D--Pad2)") (class "Default")
      (node (ref "J10") (pin "2") (pinfunction "D-_2") (pintype "passive"))
    )
    (net (code "34") (name "unconnected-(U2-EN-Pad3)") (class "Default")
      (node (ref "U2") (pin "3") (pinfunction "EN_3") (pintype "input+no_connect"))
    )
    (net (code "35") (name "unconnected-(U2-PWRGD-Pad10)") (class "Default")
      (node (ref "U2") (pin "10") (pinfunction "PWRGD_10") (pintype "output+no_connect"))
    )
    (net (code "36") (name "unconnected-(U10-OUT-Pad4)") (class "Default")
      (node (ref "U10") (pin "4") (pinfunction "OUT_4") (pintype "passive+no_connect"))
    )
  )
)
